# Peripheral.net
KiCad netlist of a schematic drawn in EAGLE
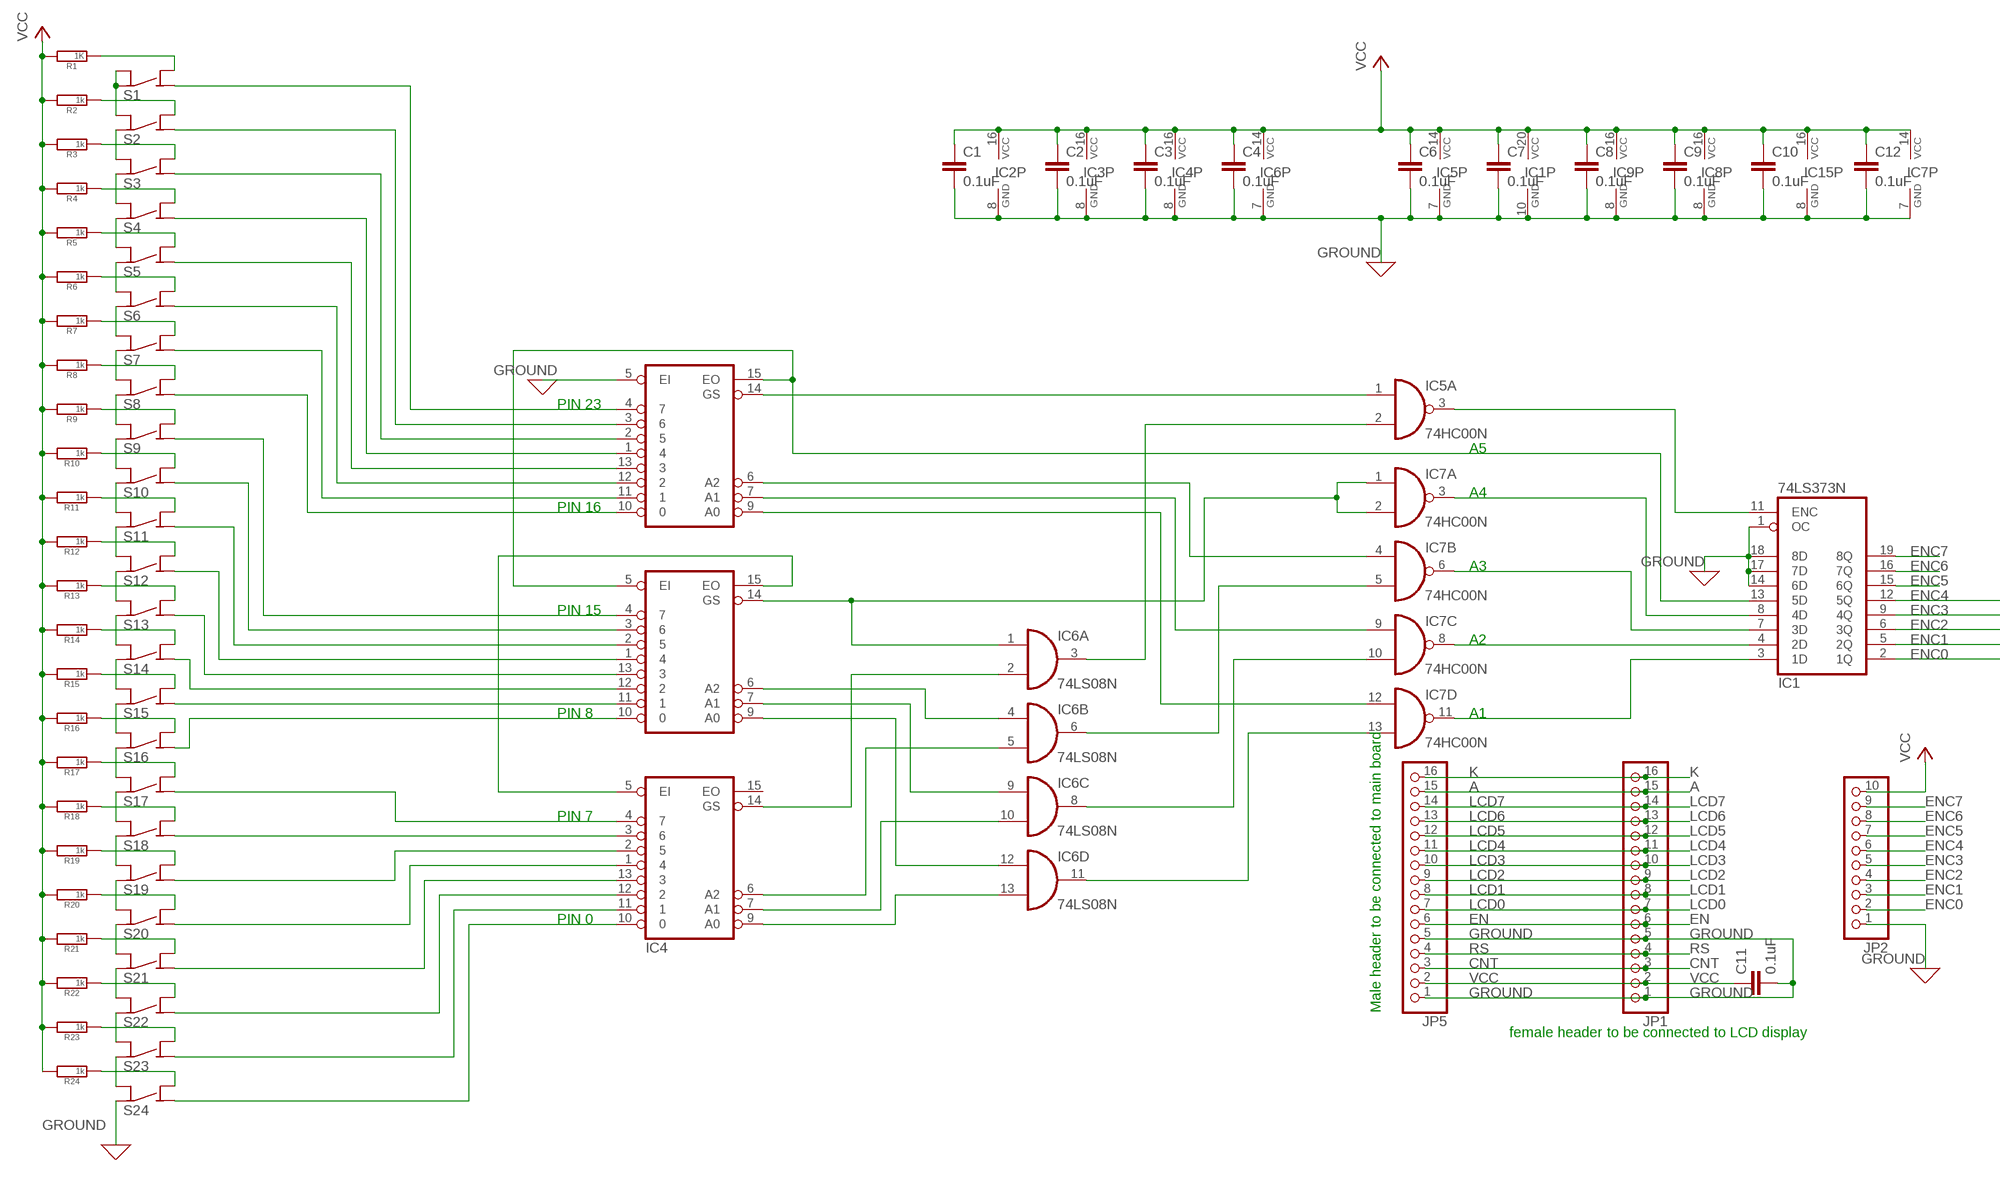
[diagram p0: schematic, sheet 1, part 1 of 2]
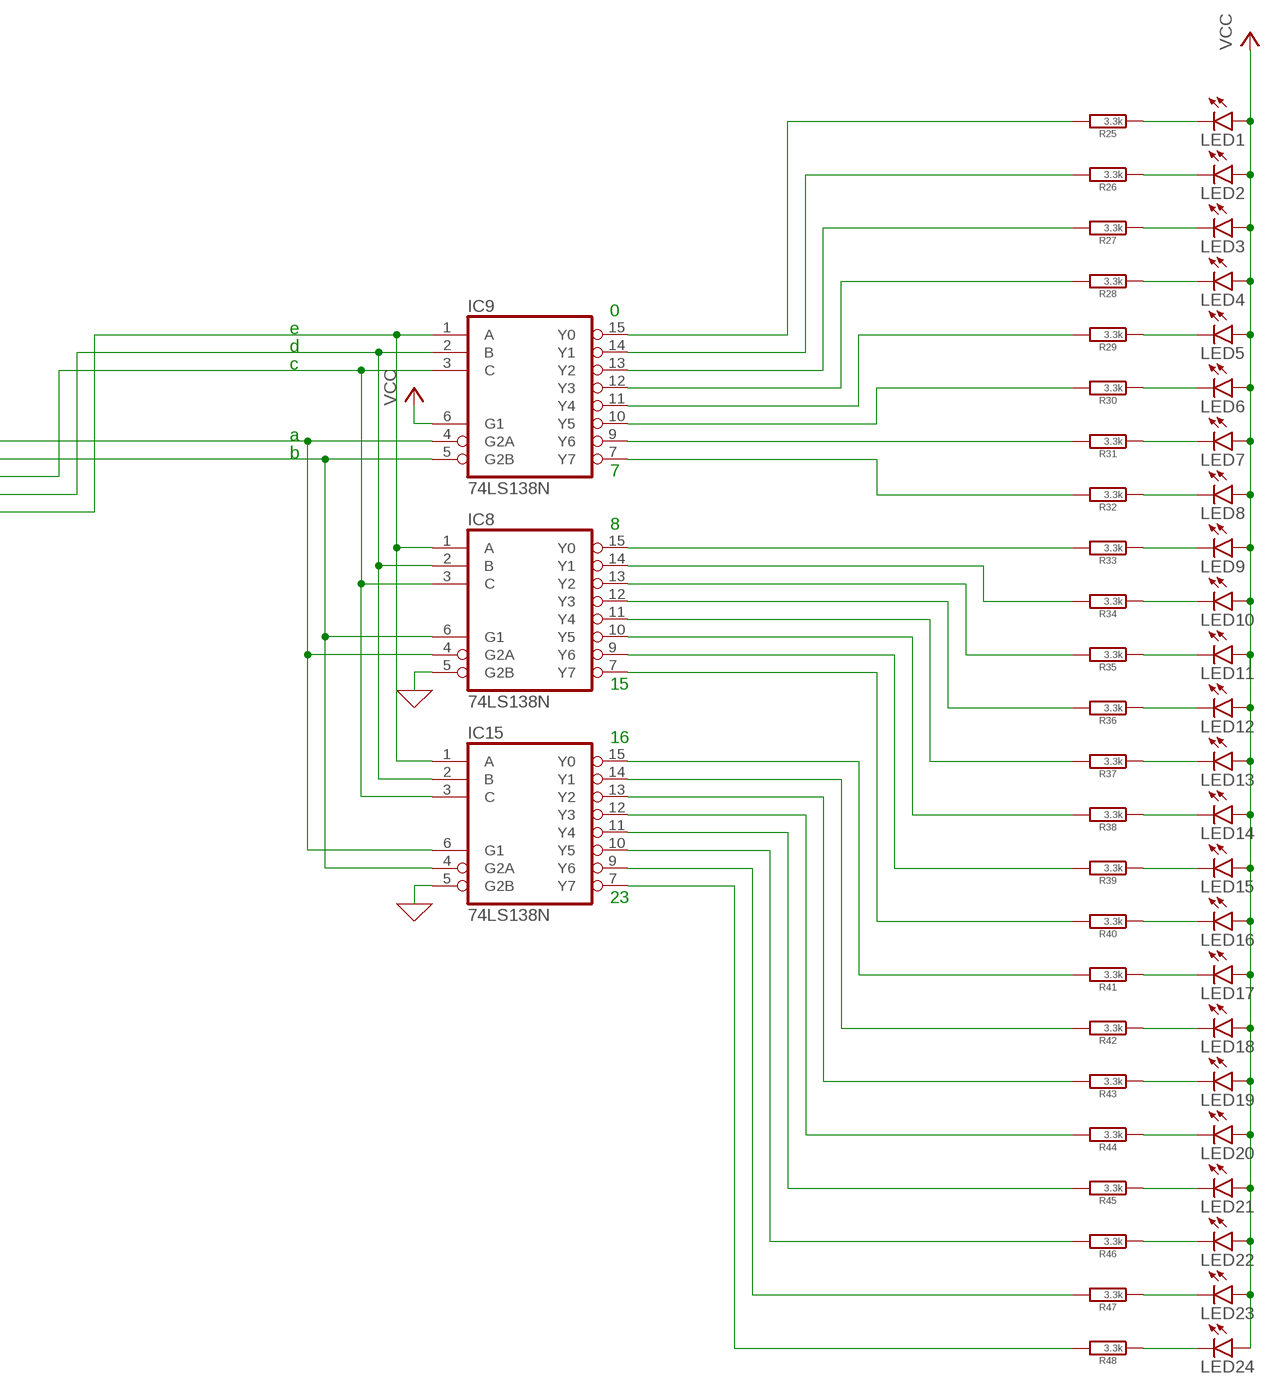
[diagram p1: schematic, sheet 1, part 2 of 2]

(export (version "E")
  (design (tool "Eeschema 10.0.6"))
  (components
    (comp (ref "C1")
      (value "0.1uF")
      (footprint "eagle-import:C2.5-2")
      (libsource (lib "eagle-import") (part "C2.5/2"))
    )
    (comp (ref "C2")
      (value "0.1uF")
      (footprint "eagle-import:C2.5-2")
      (libsource (lib "eagle-import") (part "C2.5/2"))
    )
    (comp (ref "C3")
      (value "0.1uF")
      (footprint "eagle-import:C2.5-2")
      (libsource (lib "eagle-import") (part "C2.5/2"))
    )
    (comp (ref "C4")
      (value "0.1uF")
      (footprint "eagle-import:C2.5-2")
      (libsource (lib "eagle-import") (part "C2.5/2"))
    )
    (comp (ref "C6")
      (value "0.1uF")
      (footprint "eagle-import:C2.5-2")
      (libsource (lib "eagle-import") (part "C2.5/2"))
    )
    (comp (ref "C7")
      (value "0.1uF")
      (footprint "eagle-import:C2.5-2")
      (libsource (lib "eagle-import") (part "C2.5/2"))
    )
    (comp (ref "C8")
      (value "0.1uF")
      (footprint "eagle-import:C2.5-2")
      (libsource (lib "eagle-import") (part "C2.5/2"))
    )
    (comp (ref "C9")
      (value "0.1uF")
      (footprint "eagle-import:C2.5-2")
      (libsource (lib "eagle-import") (part "C2.5/2"))
    )
    (comp (ref "C10")
      (value "0.1uF")
      (footprint "eagle-import:C2.5-2")
      (libsource (lib "eagle-import") (part "C2.5/2"))
    )
    (comp (ref "C11")
      (value "0.1uF")
      (footprint "eagle-import:C025-025X050")
      (libsource (lib "eagle-import") (part "C-EU025-025X050"))
    )
    (comp (ref "C12")
      (value "0.1uF")
      (footprint "eagle-import:C2.5-2")
      (libsource (lib "eagle-import") (part "C2.5/2"))
    )
    (comp (ref "IC1")
      (value "74LS373N")
      (footprint "eagle-import:DIL20")
      (libsource (lib "eagle-import") (part "74373NLS"))
    )
    (comp (ref "IC2")
      (value "74HC148N")
      (footprint "eagle-import:DIL16")
      (libsource (lib "eagle-import") (part "74148NHC"))
    )
    (comp (ref "IC3")
      (value "74HC148N")
      (footprint "eagle-import:DIL16")
      (libsource (lib "eagle-import") (part "74148NHC"))
    )
    (comp (ref "IC4")
      (value "74HC148N")
      (footprint "eagle-import:DIL16")
      (libsource (lib "eagle-import") (part "74148NHC"))
    )
    (comp (ref "IC5")
      (value "74HC00N")
      (footprint "eagle-import:DIL14")
      (libsource (lib "eagle-import") (part "7400NHC"))
    )
    (comp (ref "IC6")
      (value "74LS08N")
      (footprint "eagle-import:DIL14")
      (libsource (lib "eagle-import") (part "7408NLS"))
    )
    (comp (ref "IC7")
      (value "74HC00N")
      (footprint "eagle-import:DIL14")
      (libsource (lib "eagle-import") (part "7400NHC"))
    )
    (comp (ref "IC8")
      (value "74LS138N")
      (footprint "eagle-import:DIL16")
      (libsource (lib "eagle-import") (part "74138NLS"))
    )
    (comp (ref "IC9")
      (value "74LS138N")
      (footprint "eagle-import:DIL16")
      (libsource (lib "eagle-import") (part "74138NLS"))
    )
    (comp (ref "IC15")
      (value "74LS138N")
      (footprint "eagle-import:DIL16")
      (libsource (lib "eagle-import") (part "74138NLS"))
    )
    (comp (ref "JP1")
      (value "PINHD-1X16")
      (footprint "eagle-import:1X16")
      (libsource (lib "eagle-import") (part "PINHD-1X16"))
    )
    (comp (ref "JP2")
      (value "PINHD-1X10")
      (footprint "eagle-import:1X10")
      (libsource (lib "eagle-import") (part "PINHD-1X10"))
    )
    (comp (ref "JP5")
      (value "PINHD-1X16")
      (footprint "eagle-import:1X16")
      (libsource (lib "eagle-import") (part "PINHD-1X16"))
    )
    (comp (ref "LED1")
      (value "LED5MM")
      (footprint "eagle-import:LED5MM")
      (libsource (lib "eagle-import") (part "LED5MM"))
    )
    (comp (ref "LED2")
      (value "LED5MM")
      (footprint "eagle-import:LED5MM")
      (libsource (lib "eagle-import") (part "LED5MM"))
    )
    (comp (ref "LED3")
      (value "LED5MM")
      (footprint "eagle-import:LED5MM")
      (libsource (lib "eagle-import") (part "LED5MM"))
    )
    (comp (ref "LED4")
      (value "LED5MM")
      (footprint "eagle-import:LED5MM")
      (libsource (lib "eagle-import") (part "LED5MM"))
    )
    (comp (ref "LED5")
      (value "LED5MM")
      (footprint "eagle-import:LED5MM")
      (libsource (lib "eagle-import") (part "LED5MM"))
    )
    (comp (ref "LED6")
      (value "LED5MM")
      (footprint "eagle-import:LED5MM")
      (libsource (lib "eagle-import") (part "LED5MM"))
    )
    (comp (ref "LED7")
      (value "LED5MM")
      (footprint "eagle-import:LED5MM")
      (libsource (lib "eagle-import") (part "LED5MM"))
    )
    (comp (ref "LED8")
      (value "LED5MM")
      (footprint "eagle-import:LED5MM")
      (libsource (lib "eagle-import") (part "LED5MM"))
    )
    (comp (ref "LED9")
      (value "LED5MM")
      (footprint "eagle-import:LED5MM")
      (libsource (lib "eagle-import") (part "LED5MM"))
    )
    (comp (ref "LED10")
      (value "LED5MM")
      (footprint "eagle-import:LED5MM")
      (libsource (lib "eagle-import") (part "LED5MM"))
    )
    (comp (ref "LED11")
      (value "LED5MM")
      (footprint "eagle-import:LED5MM")
      (libsource (lib "eagle-import") (part "LED5MM"))
    )
    (comp (ref "LED12")
      (value "LED5MM")
      (footprint "eagle-import:LED5MM")
      (libsource (lib "eagle-import") (part "LED5MM"))
    )
    (comp (ref "LED13")
      (value "LED5MM")
      (footprint "eagle-import:LED5MM")
      (libsource (lib "eagle-import") (part "LED5MM"))
    )
    (comp (ref "LED14")
      (value "LED5MM")
      (footprint "eagle-import:LED5MM")
      (libsource (lib "eagle-import") (part "LED5MM"))
    )
    (comp (ref "LED15")
      (value "LED5MM")
      (footprint "eagle-import:LED5MM")
      (libsource (lib "eagle-import") (part "LED5MM"))
    )
    (comp (ref "LED16")
      (value "LED5MM")
      (footprint "eagle-import:LED5MM")
      (libsource (lib "eagle-import") (part "LED5MM"))
    )
    (comp (ref "LED17")
      (value "LED5MM")
      (footprint "eagle-import:LED5MM")
      (libsource (lib "eagle-import") (part "LED5MM"))
    )
    (comp (ref "LED18")
      (value "LED5MM")
      (footprint "eagle-import:LED5MM")
      (libsource (lib "eagle-import") (part "LED5MM"))
    )
    (comp (ref "LED19")
      (value "LED5MM")
      (footprint "eagle-import:LED5MM")
      (libsource (lib "eagle-import") (part "LED5MM"))
    )
    (comp (ref "LED20")
      (value "LED5MM")
      (footprint "eagle-import:LED5MM")
      (libsource (lib "eagle-import") (part "LED5MM"))
    )
    (comp (ref "LED21")
      (value "LED5MM")
      (footprint "eagle-import:LED5MM")
      (libsource (lib "eagle-import") (part "LED5MM"))
    )
    (comp (ref "LED22")
      (value "LED5MM")
      (footprint "eagle-import:LED5MM")
      (libsource (lib "eagle-import") (part "LED5MM"))
    )
    (comp (ref "LED23")
      (value "LED5MM")
      (footprint "eagle-import:LED5MM")
      (libsource (lib "eagle-import") (part "LED5MM"))
    )
    (comp (ref "LED24")
      (value "LED5MM")
      (footprint "eagle-import:LED5MM")
      (libsource (lib "eagle-import") (part "LED5MM"))
    )
    (comp (ref "R1")
      (value "1K")
      (footprint "eagle-import:1_6W(5MM)")
      (libsource (lib "eagle-import") (part "R{gt}{gt}1/6W(5MM)"))
    )
    (comp (ref "R2")
      (value "1k")
      (footprint "eagle-import:1_6W(5MM)")
      (libsource (lib "eagle-import") (part "R{gt}{gt}1/6W(5MM)"))
    )
    (comp (ref "R3")
      (value "1k")
      (footprint "eagle-import:1_6W(5MM)")
      (libsource (lib "eagle-import") (part "R{gt}{gt}1/6W(5MM)"))
    )
    (comp (ref "R4")
      (value "1k")
      (footprint "eagle-import:1_6W(5MM)")
      (libsource (lib "eagle-import") (part "R{gt}{gt}1/6W(5MM)"))
    )
    (comp (ref "R5")
      (value "1k")
      (footprint "eagle-import:1_6W(5MM)")
      (libsource (lib "eagle-import") (part "R{gt}{gt}1/6W(5MM)"))
    )
    (comp (ref "R6")
      (value "1k")
      (footprint "eagle-import:1_6W(5MM)")
      (libsource (lib "eagle-import") (part "R{gt}{gt}1/6W(5MM)"))
    )
    (comp (ref "R7")
      (value "1k")
      (footprint "eagle-import:1_6W(5MM)")
      (libsource (lib "eagle-import") (part "R{gt}{gt}1/6W(5MM)"))
    )
    (comp (ref "R8")
      (value "1k")
      (footprint "eagle-import:1_6W(5MM)")
      (libsource (lib "eagle-import") (part "R{gt}{gt}1/6W(5MM)"))
    )
    (comp (ref "R9")
      (value "1k")
      (footprint "eagle-import:1_6W(5MM)")
      (libsource (lib "eagle-import") (part "R{gt}{gt}1/6W(5MM)"))
    )
    (comp (ref "R10")
      (value "1k")
      (footprint "eagle-import:1_6W(5MM)")
      (libsource (lib "eagle-import") (part "R{gt}{gt}1/6W(5MM)"))
    )
    (comp (ref "R11")
      (value "1k")
      (footprint "eagle-import:1_6W(5MM)")
      (libsource (lib "eagle-import") (part "R{gt}{gt}1/6W(5MM)"))
    )
    (comp (ref "R12")
      (value "1k")
      (footprint "eagle-import:1_6W(5MM)")
      (libsource (lib "eagle-import") (part "R{gt}{gt}1/6W(5MM)"))
    )
    (comp (ref "R13")
      (value "1k")
      (footprint "eagle-import:1_6W(5MM)")
      (libsource (lib "eagle-import") (part "R{gt}{gt}1/6W(5MM)"))
    )
    (comp (ref "R14")
      (value "1k")
      (footprint "eagle-import:1_6W(5MM)")
      (libsource (lib "eagle-import") (part "R{gt}{gt}1/6W(5MM)"))
    )
    (comp (ref "R15")
      (value "1k")
      (footprint "eagle-import:1_6W(5MM)")
      (libsource (lib "eagle-import") (part "R{gt}{gt}1/6W(5MM)"))
    )
    (comp (ref "R16")
      (value "1k")
      (footprint "eagle-import:1_6W(5MM)")
      (libsource (lib "eagle-import") (part "R{gt}{gt}1/6W(5MM)"))
    )
    (comp (ref "R17")
      (value "1k")
      (footprint "eagle-import:1_6W(5MM)")
      (libsource (lib "eagle-import") (part "R{gt}{gt}1/6W(5MM)"))
    )
    (comp (ref "R18")
      (value "1k")
      (footprint "eagle-import:1_6W(5MM)")
      (libsource (lib "eagle-import") (part "R{gt}{gt}1/6W(5MM)"))
    )
    (comp (ref "R19")
      (value "1k")
      (footprint "eagle-import:1_6W(5MM)")
      (libsource (lib "eagle-import") (part "R{gt}{gt}1/6W(5MM)"))
    )
    (comp (ref "R20")
      (value "1k")
      (footprint "eagle-import:1_6W(5MM)")
      (libsource (lib "eagle-import") (part "R{gt}{gt}1/6W(5MM)"))
    )
    (comp (ref "R21")
      (value "1k")
      (footprint "eagle-import:1_6W(5MM)")
      (libsource (lib "eagle-import") (part "R{gt}{gt}1/6W(5MM)"))
    )
    (comp (ref "R22")
      (value "1k")
      (footprint "eagle-import:1_6W(5MM)")
      (libsource (lib "eagle-import") (part "R{gt}{gt}1/6W(5MM)"))
    )
    (comp (ref "R23")
      (value "1k")
      (footprint "eagle-import:1_6W(5MM)")
      (libsource (lib "eagle-import") (part "R{gt}{gt}1/6W(5MM)"))
    )
    (comp (ref "R24")
      (value "1k")
      (footprint "eagle-import:1_6W(5MM)")
      (libsource (lib "eagle-import") (part "R{gt}{gt}1/6W(5MM)"))
    )
    (comp (ref "R25")
      (value "3.3k")
      (footprint "eagle-import:1_6W(5MM)")
      (libsource (lib "eagle-import") (part "R{gt}{gt}1/6W(5MM)"))
    )
    (comp (ref "R26")
      (value "3.3k")
      (footprint "eagle-import:1_6W(5MM)")
      (libsource (lib "eagle-import") (part "R{gt}{gt}1/6W(5MM)"))
    )
    (comp (ref "R27")
      (value "3.3k")
      (footprint "eagle-import:1_6W(5MM)")
      (libsource (lib "eagle-import") (part "R{gt}{gt}1/6W(5MM)"))
    )
    (comp (ref "R28")
      (value "3.3k")
      (footprint "eagle-import:1_6W(5MM)")
      (libsource (lib "eagle-import") (part "R{gt}{gt}1/6W(5MM)"))
    )
    (comp (ref "R29")
      (value "3.3k")
      (footprint "eagle-import:1_6W(5MM)")
      (libsource (lib "eagle-import") (part "R{gt}{gt}1/6W(5MM)"))
    )
    (comp (ref "R30")
      (value "3.3k")
      (footprint "eagle-import:1_6W(5MM)")
      (libsource (lib "eagle-import") (part "R{gt}{gt}1/6W(5MM)"))
    )
    (comp (ref "R31")
      (value "3.3k")
      (footprint "eagle-import:1_6W(5MM)")
      (libsource (lib "eagle-import") (part "R{gt}{gt}1/6W(5MM)"))
    )
    (comp (ref "R32")
      (value "3.3k")
      (footprint "eagle-import:1_6W(5MM)")
      (libsource (lib "eagle-import") (part "R{gt}{gt}1/6W(5MM)"))
    )
    (comp (ref "R33")
      (value "3.3k")
      (footprint "eagle-import:1_6W(5MM)")
      (libsource (lib "eagle-import") (part "R{gt}{gt}1/6W(5MM)"))
    )
    (comp (ref "R34")
      (value "3.3k")
      (footprint "eagle-import:1_6W(5MM)")
      (libsource (lib "eagle-import") (part "R{gt}{gt}1/6W(5MM)"))
    )
    (comp (ref "R35")
      (value "3.3k")
      (footprint "eagle-import:1_6W(5MM)")
      (libsource (lib "eagle-import") (part "R{gt}{gt}1/6W(5MM)"))
    )
    (comp (ref "R36")
      (value "3.3k")
      (footprint "eagle-import:1_6W(5MM)")
      (libsource (lib "eagle-import") (part "R{gt}{gt}1/6W(5MM)"))
    )
    (comp (ref "R37")
      (value "3.3k")
      (footprint "eagle-import:1_6W(5MM)")
      (libsource (lib "eagle-import") (part "R{gt}{gt}1/6W(5MM)"))
    )
    (comp (ref "R38")
      (value "3.3k")
      (footprint "eagle-import:1_6W(5MM)")
      (libsource (lib "eagle-import") (part "R{gt}{gt}1/6W(5MM)"))
    )
    (comp (ref "R39")
      (value "3.3k")
      (footprint "eagle-import:1_6W(5MM)")
      (libsource (lib "eagle-import") (part "R{gt}{gt}1/6W(5MM)"))
    )
    (comp (ref "R40")
      (value "3.3k")
      (footprint "eagle-import:1_6W(5MM)")
      (libsource (lib "eagle-import") (part "R{gt}{gt}1/6W(5MM)"))
    )
    (comp (ref "R41")
      (value "3.3k")
      (footprint "eagle-import:1_6W(5MM)")
      (libsource (lib "eagle-import") (part "R{gt}{gt}1/6W(5MM)"))
    )
    (comp (ref "R42")
      (value "3.3k")
      (footprint "eagle-import:1_6W(5MM)")
      (libsource (lib "eagle-import") (part "R{gt}{gt}1/6W(5MM)"))
    )
    (comp (ref "R43")
      (value "3.3k")
      (footprint "eagle-import:1_6W(5MM)")
      (libsource (lib "eagle-import") (part "R{gt}{gt}1/6W(5MM)"))
    )
    (comp (ref "R44")
      (value "3.3k")
      (footprint "eagle-import:1_6W(5MM)")
      (libsource (lib "eagle-import") (part "R{gt}{gt}1/6W(5MM)"))
    )
    (comp (ref "R45")
      (value "3.3k")
      (footprint "eagle-import:1_6W(5MM)")
      (libsource (lib "eagle-import") (part "R{gt}{gt}1/6W(5MM)"))
    )
    (comp (ref "R46")
      (value "3.3k")
      (footprint "eagle-import:1_6W(5MM)")
      (libsource (lib "eagle-import") (part "R{gt}{gt}1/6W(5MM)"))
    )
    (comp (ref "R47")
      (value "3.3k")
      (footprint "eagle-import:1_6W(5MM)")
      (libsource (lib "eagle-import") (part "R{gt}{gt}1/6W(5MM)"))
    )
    (comp (ref "R48")
      (value "3.3k")
      (footprint "eagle-import:1_6W(5MM)")
      (libsource (lib "eagle-import") (part "R{gt}{gt}1/6W(5MM)"))
    )
    (comp (ref "S1")
      (value "SPST4B3F-10XX")
      (footprint "eagle-import:B3F-10XX")
      (libsource (lib "eagle-import") (part "SPST4B3F-10XX"))
    )
    (comp (ref "S2")
      (value "SPST4B3F-10XX")
      (footprint "eagle-import:B3F-10XX")
      (libsource (lib "eagle-import") (part "SPST4B3F-10XX"))
    )
    (comp (ref "S3")
      (value "SPST4B3F-10XX")
      (footprint "eagle-import:B3F-10XX")
      (libsource (lib "eagle-import") (part "SPST4B3F-10XX"))
    )
    (comp (ref "S4")
      (value "SPST4B3F-10XX")
      (footprint "eagle-import:B3F-10XX")
      (libsource (lib "eagle-import") (part "SPST4B3F-10XX"))
    )
    (comp (ref "S5")
      (value "SPST4B3F-10XX")
      (footprint "eagle-import:B3F-10XX")
      (libsource (lib "eagle-import") (part "SPST4B3F-10XX"))
    )
    (comp (ref "S6")
      (value "SPST4B3F-10XX")
      (footprint "eagle-import:B3F-10XX")
      (libsource (lib "eagle-import") (part "SPST4B3F-10XX"))
    )
    (comp (ref "S7")
      (value "SPST4B3F-10XX")
      (footprint "eagle-import:B3F-10XX")
      (libsource (lib "eagle-import") (part "SPST4B3F-10XX"))
    )
    (comp (ref "S8")
      (value "SPST4B3F-10XX")
      (footprint "eagle-import:B3F-10XX")
      (libsource (lib "eagle-import") (part "SPST4B3F-10XX"))
    )
    (comp (ref "S9")
      (value "SPST4B3F-10XX")
      (footprint "eagle-import:B3F-10XX")
      (libsource (lib "eagle-import") (part "SPST4B3F-10XX"))
    )
    (comp (ref "S10")
      (value "SPST4B3F-10XX")
      (footprint "eagle-import:B3F-10XX")
      (libsource (lib "eagle-import") (part "SPST4B3F-10XX"))
    )
    (comp (ref "S11")
      (value "SPST4B3F-10XX")
      (footprint "eagle-import:B3F-10XX")
      (libsource (lib "eagle-import") (part "SPST4B3F-10XX"))
    )
    (comp (ref "S12")
      (value "SPST4B3F-10XX")
      (footprint "eagle-import:B3F-10XX")
      (libsource (lib "eagle-import") (part "SPST4B3F-10XX"))
    )
    (comp (ref "S13")
      (value "SPST4B3F-10XX")
      (footprint "eagle-import:B3F-10XX")
      (libsource (lib "eagle-import") (part "SPST4B3F-10XX"))
    )
    (comp (ref "S14")
      (value "SPST4B3F-10XX")
      (footprint "eagle-import:B3F-10XX")
      (libsource (lib "eagle-import") (part "SPST4B3F-10XX"))
    )
    (comp (ref "S15")
      (value "SPST4B3F-10XX")
      (footprint "eagle-import:B3F-10XX")
      (libsource (lib "eagle-import") (part "SPST4B3F-10XX"))
    )
    (comp (ref "S16")
      (value "SPST4B3F-10XX")
      (footprint "eagle-import:B3F-10XX")
      (libsource (lib "eagle-import") (part "SPST4B3F-10XX"))
    )
    (comp (ref "S17")
      (value "SPST4B3F-10XX")
      (footprint "eagle-import:B3F-10XX")
      (libsource (lib "eagle-import") (part "SPST4B3F-10XX"))
    )
    (comp (ref "S18")
      (value "SPST4B3F-10XX")
      (footprint "eagle-import:B3F-10XX")
      (libsource (lib "eagle-import") (part "SPST4B3F-10XX"))
    )
    (comp (ref "S19")
      (value "SPST4B3F-10XX")
      (footprint "eagle-import:B3F-10XX")
      (libsource (lib "eagle-import") (part "SPST4B3F-10XX"))
    )
    (comp (ref "S20")
      (value "SPST4B3F-10XX")
      (footprint "eagle-import:B3F-10XX")
      (libsource (lib "eagle-import") (part "SPST4B3F-10XX"))
    )
    (comp (ref "S21")
      (value "SPST4B3F-10XX")
      (footprint "eagle-import:B3F-10XX")
      (libsource (lib "eagle-import") (part "SPST4B3F-10XX"))
    )
    (comp (ref "S22")
      (value "SPST4B3F-10XX")
      (footprint "eagle-import:B3F-10XX")
      (libsource (lib "eagle-import") (part "SPST4B3F-10XX"))
    )
    (comp (ref "S23")
      (value "SPST4B3F-10XX")
      (footprint "eagle-import:B3F-10XX")
      (libsource (lib "eagle-import") (part "SPST4B3F-10XX"))
    )
    (comp (ref "S24")
      (value "SPST4B3F-10XX")
      (footprint "eagle-import:B3F-10XX")
      (libsource (lib "eagle-import") (part "SPST4B3F-10XX"))
    )
  )
  (nets
    (net (code "1") (name "/A") (class "Default")
      (node (ref "JP1") (pin "15") (pinfunction "15_15") (pintype "passive"))
      (node (ref "JP5") (pin "15") (pinfunction "15_15") (pintype "passive"))
    )
    (net (code "2") (name "/CNT") (class "Default")
      (node (ref "JP1") (pin "3") (pinfunction "3_3") (pintype "passive"))
      (node (ref "JP5") (pin "3") (pinfunction "3_3") (pintype "passive"))
    )
    (net (code "3") (name "/EN") (class "Default")
      (node (ref "JP1") (pin "6") (pinfunction "6_6") (pintype "passive"))
      (node (ref "JP5") (pin "6") (pinfunction "6_6") (pintype "passive"))
    )
    (net (code "4") (name "/ENC0") (class "Default")
      (node (ref "IC1") (pin "2") (pinfunction "1Q_2") (pintype "tri_state"))
      (node (ref "IC15") (pin "1") (pinfunction "A_1") (pintype "input"))
      (node (ref "IC8") (pin "1") (pinfunction "A_1") (pintype "input"))
      (node (ref "IC9") (pin "1") (pinfunction "A_1") (pintype "input"))
      (node (ref "JP2") (pin "2") (pinfunction "2_2") (pintype "passive"))
    )
    (net (code "5") (name "/ENC1") (class "Default")
      (node (ref "IC1") (pin "5") (pinfunction "2Q_5") (pintype "tri_state"))
      (node (ref "IC15") (pin "2") (pinfunction "B_2") (pintype "input"))
      (node (ref "IC8") (pin "2") (pinfunction "B_2") (pintype "input"))
      (node (ref "IC9") (pin "2") (pinfunction "B_2") (pintype "input"))
      (node (ref "JP2") (pin "3") (pinfunction "3_3") (pintype "passive"))
    )
    (net (code "6") (name "/ENC2") (class "Default")
      (node (ref "IC1") (pin "6") (pinfunction "3Q_6") (pintype "tri_state"))
      (node (ref "IC15") (pin "3") (pinfunction "C_3") (pintype "input"))
      (node (ref "IC8") (pin "3") (pinfunction "C_3") (pintype "input"))
      (node (ref "IC9") (pin "3") (pinfunction "C_3") (pintype "input"))
      (node (ref "JP2") (pin "4") (pinfunction "4_4") (pintype "passive"))
    )
    (net (code "7") (name "/ENC3") (class "Default")
      (node (ref "IC1") (pin "9") (pinfunction "4Q_9") (pintype "tri_state"))
      (node (ref "IC15") (pin "4") (pinfunction "G2A_4") (pintype "input"))
      (node (ref "IC8") (pin "6") (pinfunction "G1_6") (pintype "input"))
      (node (ref "IC9") (pin "5") (pinfunction "G2B_5") (pintype "input"))
      (node (ref "JP2") (pin "5") (pinfunction "5_5") (pintype "passive"))
    )
    (net (code "8") (name "/ENC4") (class "Default")
      (node (ref "IC1") (pin "12") (pinfunction "5Q_12") (pintype "tri_state"))
      (node (ref "IC15") (pin "6") (pinfunction "G1_6") (pintype "input"))
      (node (ref "IC8") (pin "4") (pinfunction "G2A_4") (pintype "input"))
      (node (ref "IC9") (pin "4") (pinfunction "G2A_4") (pintype "input"))
      (node (ref "JP2") (pin "6") (pinfunction "6_6") (pintype "passive"))
    )
    (net (code "9") (name "/ENC5") (class "Default")
      (node (ref "IC1") (pin "15") (pinfunction "6Q_15") (pintype "tri_state"))
      (node (ref "JP2") (pin "7") (pinfunction "7_7") (pintype "passive"))
    )
    (net (code "10") (name "/ENC6") (class "Default")
      (node (ref "IC1") (pin "16") (pinfunction "7Q_16") (pintype "tri_state"))
      (node (ref "JP2") (pin "8") (pinfunction "8_8") (pintype "passive"))
    )
    (net (code "11") (name "/ENC7") (class "Default")
      (node (ref "IC1") (pin "19") (pinfunction "8Q_19") (pintype "tri_state"))
      (node (ref "JP2") (pin "9") (pinfunction "9_9") (pintype "passive"))
    )
    (net (code "12") (name "/K") (class "Default")
      (node (ref "JP1") (pin "16") (pinfunction "16_16") (pintype "passive"))
      (node (ref "JP5") (pin "16") (pinfunction "16_16") (pintype "passive"))
    )
    (net (code "13") (name "/LCD0") (class "Default")
      (node (ref "JP1") (pin "7") (pinfunction "7_7") (pintype "passive"))
      (node (ref "JP5") (pin "7") (pinfunction "7_7") (pintype "passive"))
    )
    (net (code "14") (name "/LCD1") (class "Default")
      (node (ref "JP1") (pin "8") (pinfunction "8_8") (pintype "passive"))
      (node (ref "JP5") (pin "8") (pinfunction "8_8") (pintype "passive"))
    )
    (net (code "15") (name "/LCD2") (class "Default")
      (node (ref "JP1") (pin "9") (pinfunction "9_9") (pintype "passive"))
      (node (ref "JP5") (pin "9") (pinfunction "9_9") (pintype "passive"))
    )
    (net (code "16") (name "/LCD3") (class "Default")
      (node (ref "JP1") (pin "10") (pinfunction "10_10") (pintype "passive"))
      (node (ref "JP5") (pin "10") (pinfunction "10_10") (pintype "passive"))
    )
    (net (code "17") (name "/LCD4") (class "Default")
      (node (ref "JP1") (pin "11") (pinfunction "11_11") (pintype "passive"))
      (node (ref "JP5") (pin "11") (pinfunction "11_11") (pintype "passive"))
    )
    (net (code "18") (name "/LCD5") (class "Default")
      (node (ref "JP1") (pin "12") (pinfunction "12_12") (pintype "passive"))
      (node (ref "JP5") (pin "12") (pinfunction "12_12") (pintype "passive"))
    )
    (net (code "19") (name "/LCD6") (class "Default")
      (node (ref "JP1") (pin "13") (pinfunction "13_13") (pintype "passive"))
      (node (ref "JP5") (pin "13") (pinfunction "13_13") (pintype "passive"))
    )
    (net (code "20") (name "/LCD7") (class "Default")
      (node (ref "JP1") (pin "14") (pinfunction "14_14") (pintype "passive"))
      (node (ref "JP5") (pin "14") (pinfunction "14_14") (pintype "passive"))
    )
    (net (code "21") (name "/RS") (class "Default")
      (node (ref "JP1") (pin "4") (pinfunction "4_4") (pintype "passive"))
      (node (ref "JP5") (pin "4") (pinfunction "4_4") (pintype "passive"))
    )
    (net (code "22") (name "GND") (class "Default")
      (node (ref "C1") (pin "2") (pinfunction "2_2") (pintype "passive"))
      (node (ref "C10") (pin "2") (pinfunction "2_2") (pintype "passive"))
      (node (ref "C11") (pin "2") (pinfunction "2_2") (pintype "passive"))
      (node (ref "C12") (pin "2") (pinfunction "2_2") (pintype "passive"))
      (node (ref "C2") (pin "2") (pinfunction "2_2") (pintype "passive"))
      (node (ref "C3") (pin "2") (pinfunction "2_2") (pintype "passive"))
      (node (ref "C4") (pin "2") (pinfunction "2_2") (pintype "passive"))
      (node (ref "C6") (pin "2") (pinfunction "2_2") (pintype "passive"))
      (node (ref "C7") (pin "2") (pinfunction "2_2") (pintype "passive"))
      (node (ref "C8") (pin "2") (pinfunction "2_2") (pintype "passive"))
      (node (ref "C9") (pin "2") (pinfunction "2_2") (pintype "passive"))
      (node (ref "IC1") (pin "1") (pinfunction "OC_1") (pintype "input"))
      (node (ref "IC1") (pin "10") (pinfunction "GND_10") (pintype "power_in"))
      (node (ref "IC1") (pin "14") (pinfunction "6D_14") (pintype "input"))
      (node (ref "IC1") (pin "17") (pinfunction "7D_17") (pintype "input"))
      (node (ref "IC1") (pin "18") (pinfunction "8D_18") (pintype "input"))
      (node (ref "IC15") (pin "5") (pinfunction "G2B_5") (pintype "input"))
      (node (ref "IC15") (pin "8") (pinfunction "GND_8") (pintype "power_in"))
      (node (ref "IC2") (pin "5") (pinfunction "EI_5") (pintype "input"))
      (node (ref "IC2") (pin "8") (pinfunction "GND_8") (pintype "power_in"))
      (node (ref "IC3") (pin "8") (pinfunction "GND_8") (pintype "power_in"))
      (node (ref "IC4") (pin "8") (pinfunction "GND_8") (pintype "power_in"))
      (node (ref "IC5") (pin "7") (pinfunction "GND_7") (pintype "power_in"))
      (node (ref "IC6") (pin "7") (pinfunction "GND_7") (pintype "power_in"))
      (node (ref "IC7") (pin "7") (pinfunction "GND_7") (pintype "power_in"))
      (node (ref "IC8") (pin "5") (pinfunction "G2B_5") (pintype "input"))
      (node (ref "IC8") (pin "8") (pinfunction "GND_8") (pintype "power_in"))
      (node (ref "IC9") (pin "8") (pinfunction "GND_8") (pintype "power_in"))
      (node (ref "JP1") (pin "1") (pinfunction "1_1") (pintype "passive"))
      (node (ref "JP1") (pin "5") (pinfunction "5_5") (pintype "passive"))
      (node (ref "JP2") (pin "1") (pinfunction "1_1") (pintype "passive"))
      (node (ref "JP5") (pin "1") (pinfunction "1_1") (pintype "passive"))
      (node (ref "JP5") (pin "5") (pinfunction "5_5") (pintype "passive"))
      (node (ref "S1") (pin "COM@1") (pinfunction "COM_COM@1") (pintype "passive"))
      (node (ref "S1") (pin "COM@2") (pinfunction "COM_COM@2") (pintype "passive"))
      (node (ref "S10") (pin "COM@1") (pinfunction "COM_COM@1") (pintype "passive"))
      (node (ref "S10") (pin "COM@2") (pinfunction "COM_COM@2") (pintype "passive"))
      (node (ref "S11") (pin "COM@1") (pinfunction "COM_COM@1") (pintype "passive"))
      (node (ref "S11") (pin "COM@2") (pinfunction "COM_COM@2") (pintype "passive"))
      (node (ref "S12") (pin "COM@1") (pinfunction "COM_COM@1") (pintype "passive"))
      (node (ref "S12") (pin "COM@2") (pinfunction "COM_COM@2") (pintype "passive"))
      (node (ref "S13") (pin "COM@1") (pinfunction "COM_COM@1") (pintype "passive"))
      (node (ref "S13") (pin "COM@2") (pinfunction "COM_COM@2") (pintype "passive"))
      (node (ref "S14") (pin "COM@1") (pinfunction "COM_COM@1") (pintype "passive"))
      (node (ref "S14") (pin "COM@2") (pinfunction "COM_COM@2") (pintype "passive"))
      (node (ref "S15") (pin "COM@1") (pinfunction "COM_COM@1") (pintype "passive"))
      (node (ref "S15") (pin "COM@2") (pinfunction "COM_COM@2") (pintype "passive"))
      (node (ref "S16") (pin "COM@1") (pinfunction "COM_COM@1") (pintype "passive"))
      (node (ref "S16") (pin "COM@2") (pinfunction "COM_COM@2") (pintype "passive"))
      (node (ref "S17") (pin "COM@1") (pinfunction "COM_COM@1") (pintype "passive"))
      (node (ref "S17") (pin "COM@2") (pinfunction "COM_COM@2") (pintype "passive"))
      (node (ref "S18") (pin "COM@1") (pinfunction "COM_COM@1") (pintype "passive"))
      (node (ref "S18") (pin "COM@2") (pinfunction "COM_COM@2") (pintype "passive"))
      (node (ref "S19") (pin "COM@1") (pinfunction "COM_COM@1") (pintype "passive"))
      (node (ref "S19") (pin "COM@2") (pinfunction "COM_COM@2") (pintype "passive"))
      (node (ref "S2") (pin "COM@1") (pinfunction "COM_COM@1") (pintype "passive"))
      (node (ref "S2") (pin "COM@2") (pinfunction "COM_COM@2") (pintype "passive"))
      (node (ref "S20") (pin "COM@1") (pinfunction "COM_COM@1") (pintype "passive"))
      (node (ref "S20") (pin "COM@2") (pinfunction "COM_COM@2") (pintype "passive"))
      (node (ref "S21") (pin "COM@1") (pinfunction "COM_COM@1") (pintype "passive"))
      (node (ref "S21") (pin "COM@2") (pinfunction "COM_COM@2") (pintype "passive"))
      (node (ref "S22") (pin "COM@1") (pinfunction "COM_COM@1") (pintype "passive"))
      (node (ref "S22") (pin "COM@2") (pinfunction "COM_COM@2") (pintype "passive"))
      (node (ref "S23") (pin "COM@1") (pinfunction "COM_COM@1") (pintype "passive"))
      (node (ref "S23") (pin "COM@2") (pinfunction "COM_COM@2") (pintype "passive"))
      (node (ref "S24") (pin "COM@1") (pinfunction "COM_COM@1") (pintype "passive"))
      (node (ref "S24") (pin "COM@2") (pinfunction "COM_COM@2") (pintype "passive"))
      (node (ref "S3") (pin "COM@1") (pinfunction "COM_COM@1") (pintype "passive"))
      (node (ref "S3") (pin "COM@2") (pinfunction "COM_COM@2") (pintype "passive"))
      (node (ref "S4") (pin "COM@1") (pinfunction "COM_COM@1") (pintype "passive"))
      (node (ref "S4") (pin "COM@2") (pinfunction "COM_COM@2") (pintype "passive"))
      (node (ref "S5") (pin "COM@1") (pinfunction "COM_COM@1") (pintype "passive"))
      (node (ref "S5") (pin "COM@2") (pinfunction "COM_COM@2") (pintype "passive"))
      (node (ref "S6") (pin "COM@1") (pinfunction "COM_COM@1") (pintype "passive"))
      (node (ref "S6") (pin "COM@2") (pinfunction "COM_COM@2") (pintype "passive"))
      (node (ref "S7") (pin "COM@1") (pinfunction "COM_COM@1") (pintype "passive"))
      (node (ref "S7") (pin "COM@2") (pinfunction "COM_COM@2") (pintype "passive"))
      (node (ref "S8") (pin "COM@1") (pinfunction "COM_COM@1") (pintype "passive"))
      (node (ref "S8") (pin "COM@2") (pinfunction "COM_COM@2") (pintype "passive"))
      (node (ref "S9") (pin "COM@1") (pinfunction "COM_COM@1") (pintype "passive"))
      (node (ref "S9") (pin "COM@2") (pinfunction "COM_COM@2") (pintype "passive"))
    )
    (net (code "23") (name "Net-(IC1A-1D)") (class "Default")
      (node (ref "IC1") (pin "3") (pinfunction "1D_3") (pintype "input"))
      (node (ref "IC7") (pin "11") (pinfunction "O_11") (pintype "output"))
    )
    (net (code "24") (name "Net-(IC1A-2D)") (class "Default")
      (node (ref "IC1") (pin "4") (pinfunction "2D_4") (pintype "input"))
      (node (ref "IC7") (pin "8") (pinfunction "O_8") (pintype "output"))
    )
    (net (code "25") (name "Net-(IC1A-3D)") (class "Default")
      (node (ref "IC1") (pin "7") (pinfunction "3D_7") (pintype "input"))
      (node (ref "IC7") (pin "6") (pinfunction "O_6") (pintype "output"))
    )
    (net (code "26") (name "Net-(IC1A-4D)") (class "Default")
      (node (ref "IC1") (pin "8") (pinfunction "4D_8") (pintype "input"))
      (node (ref "IC7") (pin "3") (pinfunction "O_3") (pintype "output"))
    )
    (net (code "27") (name "Net-(IC1A-5D)") (class "Default")
      (node (ref "IC1") (pin "13") (pinfunction "5D_13") (pintype "input"))
      (node (ref "IC2") (pin "15") (pinfunction "EO_15") (pintype "output"))
      (node (ref "IC3") (pin "5") (pinfunction "EI_5") (pintype "input"))
    )
    (net (code "28") (name "Net-(IC1A-ENC)") (class "Default")
      (node (ref "IC1") (pin "11") (pinfunction "ENC_11") (pintype "input"))
      (node (ref "IC5") (pin "3") (pinfunction "O_3") (pintype "output"))
    )
    (net (code "29") (name "Net-(IC2A-0)") (class "Default")
      (node (ref "IC2") (pin "10") (pinfunction "0_10") (pintype "input"))
      (node (ref "S8") (pin "NO@1") (pinfunction "NO_NO@1") (pintype "passive"))
    )
    (net (code "30") (name "Net-(IC2A-1)") (class "Default")
      (node (ref "IC2") (pin "11") (pinfunction "1_11") (pintype "input"))
      (node (ref "S7") (pin "NO@1") (pinfunction "NO_NO@1") (pintype "passive"))
    )
    (net (code "31") (name "Net-(IC2A-2)") (class "Default")
      (node (ref "IC2") (pin "12") (pinfunction "2_12") (pintype "input"))
      (node (ref "S6") (pin "NO@1") (pinfunction "NO_NO@1") (pintype "passive"))
    )
    (net (code "32") (name "Net-(IC2A-3)") (class "Default")
      (node (ref "IC2") (pin "13") (pinfunction "3_13") (pintype "input"))
      (node (ref "S5") (pin "NO@1") (pinfunction "NO_NO@1") (pintype "passive"))
    )
    (net (code "33") (name "Net-(IC2A-4)") (class "Default")
      (node (ref "IC2") (pin "1") (pinfunction "4_1") (pintype "input"))
      (node (ref "S4") (pin "NO@1") (pinfunction "NO_NO@1") (pintype "passive"))
    )
    (net (code "34") (name "Net-(IC2A-5)") (class "Default")
      (node (ref "IC2") (pin "2") (pinfunction "5_2") (pintype "input"))
      (node (ref "S3") (pin "NO@1") (pinfunction "NO_NO@1") (pintype "passive"))
    )
    (net (code "35") (name "Net-(IC2A-6)") (class "Default")
      (node (ref "IC2") (pin "3") (pinfunction "6_3") (pintype "input"))
      (node (ref "S2") (pin "NO@1") (pinfunction "NO_NO@1") (pintype "passive"))
    )
    (net (code "36") (name "Net-(IC2A-7)") (class "Default")
      (node (ref "IC2") (pin "4") (pinfunction "7_4") (pintype "input"))
      (node (ref "S1") (pin "NO@1") (pinfunction "NO_NO@1") (pintype "passive"))
    )
    (net (code "37") (name "Net-(IC2A-A0)") (class "Default")
      (node (ref "IC2") (pin "9") (pinfunction "A0_9") (pintype "output"))
      (node (ref "IC7") (pin "12") (pinfunction "I0_12") (pintype "input"))
    )
    (net (code "38") (name "Net-(IC2A-A1)") (class "Default")
      (node (ref "IC2") (pin "7") (pinfunction "A1_7") (pintype "output"))
      (node (ref "IC7") (pin "9") (pinfunction "I0_9") (pintype "input"))
    )
    (net (code "39") (name "Net-(IC2A-A2)") (class "Default")
      (node (ref "IC2") (pin "6") (pinfunction "A2_6") (pintype "output"))
      (node (ref "IC7") (pin "4") (pinfunction "I0_4") (pintype "input"))
    )
    (net (code "40") (name "Net-(IC2A-GS)") (class "Default")
      (node (ref "IC2") (pin "14") (pinfunction "GS_14") (pintype "output"))
      (node (ref "IC5") (pin "1") (pinfunction "I0_1") (pintype "input"))
    )
    (net (code "41") (name "Net-(IC3A-0)") (class "Default")
      (node (ref "IC3") (pin "10") (pinfunction "0_10") (pintype "input"))
      (node (ref "S16") (pin "NO@1") (pinfunction "NO_NO@1") (pintype "passive"))
    )
    (net (code "42") (name "Net-(IC3A-1)") (class "Default")
      (node (ref "IC3") (pin "11") (pinfunction "1_11") (pintype "input"))
      (node (ref "S15") (pin "NO@1") (pinfunction "NO_NO@1") (pintype "passive"))
    )
    (net (code "43") (name "Net-(IC3A-2)") (class "Default")
      (node (ref "IC3") (pin "12") (pinfunction "2_12") (pintype "input"))
      (node (ref "S14") (pin "NO@1") (pinfunction "NO_NO@1") (pintype "passive"))
    )
    (net (code "44") (name "Net-(IC3A-3)") (class "Default")
      (node (ref "IC3") (pin "13") (pinfunction "3_13") (pintype "input"))
      (node (ref "S13") (pin "NO@1") (pinfunction "NO_NO@1") (pintype "passive"))
    )
    (net (code "45") (name "Net-(IC3A-4)") (class "Default")
      (node (ref "IC3") (pin "1") (pinfunction "4_1") (pintype "input"))
      (node (ref "S12") (pin "NO@1") (pinfunction "NO_NO@1") (pintype "passive"))
    )
    (net (code "46") (name "Net-(IC3A-5)") (class "Default")
      (node (ref "IC3") (pin "2") (pinfunction "5_2") (pintype "input"))
      (node (ref "S11") (pin "NO@1") (pinfunction "NO_NO@1") (pintype "passive"))
    )
    (net (code "47") (name "Net-(IC3A-6)") (class "Default")
      (node (ref "IC3") (pin "3") (pinfunction "6_3") (pintype "input"))
      (node (ref "S10") (pin "NO@1") (pinfunction "NO_NO@1") (pintype "passive"))
    )
    (net (code "48") (name "Net-(IC3A-7)") (class "Default")
      (node (ref "IC3") (pin "4") (pinfunction "7_4") (pintype "input"))
      (node (ref "S9") (pin "NO@1") (pinfunction "NO_NO@1") (pintype "passive"))
    )
    (net (code "49") (name "Net-(IC3A-A0)") (class "Default")
      (node (ref "IC3") (pin "9") (pinfunction "A0_9") (pintype "output"))
      (node (ref "IC6") (pin "12") (pinfunction "I0_12") (pintype "input"))
    )
    (net (code "50") (name "Net-(IC3A-A1)") (class "Default")
      (node (ref "IC3") (pin "7") (pinfunction "A1_7") (pintype "output"))
      (node (ref "IC6") (pin "9") (pinfunction "I0_9") (pintype "input"))
    )
    (net (code "51") (name "Net-(IC3A-A2)") (class "Default")
      (node (ref "IC3") (pin "6") (pinfunction "A2_6") (pintype "output"))
      (node (ref "IC6") (pin "4") (pinfunction "I0_4") (pintype "input"))
    )
    (net (code "52") (name "Net-(IC3A-EO)") (class "Default")
      (node (ref "IC3") (pin "15") (pinfunction "EO_15") (pintype "output"))
      (node (ref "IC4") (pin "5") (pinfunction "EI_5") (pintype "input"))
    )
    (net (code "53") (name "Net-(IC3A-GS)") (class "Default")
      (node (ref "IC3") (pin "14") (pinfunction "GS_14") (pintype "output"))
      (node (ref "IC6") (pin "1") (pinfunction "I0_1") (pintype "input"))
      (node (ref "IC7") (pin "1") (pinfunction "I0_1") (pintype "input"))
      (node (ref "IC7") (pin "2") (pinfunction "I1_2") (pintype "input"))
    )
    (net (code "54") (name "Net-(IC4A-0)") (class "Default")
      (node (ref "IC4") (pin "10") (pinfunction "0_10") (pintype "input"))
      (node (ref "S24") (pin "NO@1") (pinfunction "NO_NO@1") (pintype "passive"))
    )
    (net (code "55") (name "Net-(IC4A-1)") (class "Default")
      (node (ref "IC4") (pin "11") (pinfunction "1_11") (pintype "input"))
      (node (ref "S23") (pin "NO@1") (pinfunction "NO_NO@1") (pintype "passive"))
    )
    (net (code "56") (name "Net-(IC4A-2)") (class "Default")
      (node (ref "IC4") (pin "12") (pinfunction "2_12") (pintype "input"))
      (node (ref "S22") (pin "NO@1") (pinfunction "NO_NO@1") (pintype "passive"))
    )
    (net (code "57") (name "Net-(IC4A-3)") (class "Default")
      (node (ref "IC4") (pin "13") (pinfunction "3_13") (pintype "input"))
      (node (ref "S21") (pin "NO@1") (pinfunction "NO_NO@1") (pintype "passive"))
    )
    (net (code "58") (name "Net-(IC4A-4)") (class "Default")
      (node (ref "IC4") (pin "1") (pinfunction "4_1") (pintype "input"))
      (node (ref "S20") (pin "NO@1") (pinfunction "NO_NO@1") (pintype "passive"))
    )
    (net (code "59") (name "Net-(IC4A-5)") (class "Default")
      (node (ref "IC4") (pin "2") (pinfunction "5_2") (pintype "input"))
      (node (ref "S19") (pin "NO@1") (pinfunction "NO_NO@1") (pintype "passive"))
    )
    (net (code "60") (name "Net-(IC4A-6)") (class "Default")
      (node (ref "IC4") (pin "3") (pinfunction "6_3") (pintype "input"))
      (node (ref "S18") (pin "NO@1") (pinfunction "NO_NO@1") (pintype "passive"))
    )
    (net (code "61") (name "Net-(IC4A-7)") (class "Default")
      (node (ref "IC4") (pin "4") (pinfunction "7_4") (pintype "input"))
      (node (ref "S17") (pin "NO@1") (pinfunction "NO_NO@1") (pintype "passive"))
    )
    (net (code "62") (name "Net-(IC4A-A0)") (class "Default")
      (node (ref "IC4") (pin "9") (pinfunction "A0_9") (pintype "output"))
      (node (ref "IC6") (pin "13") (pinfunction "I1_13") (pintype "input"))
    )
    (net (code "63") (name "Net-(IC4A-A1)") (class "Default")
      (node (ref "IC4") (pin "7") (pinfunction "A1_7") (pintype "output"))
      (node (ref "IC6") (pin "10") (pinfunction "I1_10") (pintype "input"))
    )
    (net (code "64") (name "Net-(IC4A-A2)") (class "Default")
      (node (ref "IC4") (pin "6") (pinfunction "A2_6") (pintype "output"))
      (node (ref "IC6") (pin "5") (pinfunction "I1_5") (pintype "input"))
    )
    (net (code "65") (name "Net-(IC4A-GS)") (class "Default")
      (node (ref "IC4") (pin "14") (pinfunction "GS_14") (pintype "output"))
      (node (ref "IC6") (pin "2") (pinfunction "I1_2") (pintype "input"))
    )
    (net (code "66") (name "Net-(IC5A-I1)") (class "Default")
      (node (ref "IC5") (pin "2") (pinfunction "I1_2") (pintype "input"))
      (node (ref "IC6") (pin "3") (pinfunction "O_3") (pintype "output"))
    )
    (net (code "67") (name "Net-(IC6B-O)") (class "Default")
      (node (ref "IC6") (pin "6") (pinfunction "O_6") (pintype "output"))
      (node (ref "IC7") (pin "5") (pinfunction "I1_5") (pintype "input"))
    )
    (net (code "68") (name "Net-(IC6C-O)") (class "Default")
      (node (ref "IC6") (pin "8") (pinfunction "O_8") (pintype "output"))
      (node (ref "IC7") (pin "10") (pinfunction "I1_10") (pintype "input"))
    )
    (net (code "69") (name "Net-(IC6D-O)") (class "Default")
      (node (ref "IC6") (pin "11") (pinfunction "O_11") (pintype "output"))
      (node (ref "IC7") (pin "13") (pinfunction "I1_13") (pintype "input"))
    )
    (net (code "70") (name "Net-(IC8A-Y0)") (class "Default")
      (node (ref "IC8") (pin "15") (pinfunction "Y0_15") (pintype "output"))
      (node (ref "R33") (pin "2") (pinfunction "2_2") (pintype "passive"))
    )
    (net (code "71") (name "Net-(IC8A-Y1)") (class "Default")
      (node (ref "IC8") (pin "14") (pinfunction "Y1_14") (pintype "output"))
      (node (ref "R34") (pin "2") (pinfunction "2_2") (pintype "passive"))
    )
    (net (code "72") (name "Net-(IC8A-Y2)") (class "Default")
      (node (ref "IC8") (pin "13") (pinfunction "Y2_13") (pintype "output"))
      (node (ref "R35") (pin "2") (pinfunction "2_2") (pintype "passive"))
    )
    (net (code "73") (name "Net-(IC8A-Y3)") (class "Default")
      (node (ref "IC8") (pin "12") (pinfunction "Y3_12") (pintype "output"))
      (node (ref "R36") (pin "2") (pinfunction "2_2") (pintype "passive"))
    )
    (net (code "74") (name "Net-(IC8A-Y4)") (class "Default")
      (node (ref "IC8") (pin "11") (pinfunction "Y4_11") (pintype "output"))
      (node (ref "R37") (pin "2") (pinfunction "2_2") (pintype "passive"))
    )
    (net (code "75") (name "Net-(IC8A-Y5)") (class "Default")
      (node (ref "IC8") (pin "10") (pinfunction "Y5_10") (pintype "output"))
      (node (ref "R38") (pin "2") (pinfunction "2_2") (pintype "passive"))
    )
    (net (code "76") (name "Net-(IC8A-Y6)") (class "Default")
      (node (ref "IC8") (pin "9") (pinfunction "Y6_9") (pintype "output"))
      (node (ref "R39") (pin "2") (pinfunction "2_2") (pintype "passive"))
    )
    (net (code "77") (name "Net-(IC8A-Y7)") (class "Default")
      (node (ref "IC8") (pin "7") (pinfunction "Y7_7") (pintype "output"))
      (node (ref "R40") (pin "2") (pinfunction "2_2") (pintype "passive"))
    )
    (net (code "78") (name "Net-(IC9A-Y0)") (class "Default")
      (node (ref "IC9") (pin "15") (pinfunction "Y0_15") (pintype "output"))
      (node (ref "R25") (pin "2") (pinfunction "2_2") (pintype "passive"))
    )
    (net (code "79") (name "Net-(IC9A-Y1)") (class "Default")
      (node (ref "IC9") (pin "14") (pinfunction "Y1_14") (pintype "output"))
      (node (ref "R26") (pin "2") (pinfunction "2_2") (pintype "passive"))
    )
    (net (code "80") (name "Net-(IC9A-Y2)") (class "Default")
      (node (ref "IC9") (pin "13") (pinfunction "Y2_13") (pintype "output"))
      (node (ref "R27") (pin "2") (pinfunction "2_2") (pintype "passive"))
    )
    (net (code "81") (name "Net-(IC9A-Y3)") (class "Default")
      (node (ref "IC9") (pin "12") (pinfunction "Y3_12") (pintype "output"))
      (node (ref "R28") (pin "2") (pinfunction "2_2") (pintype "passive"))
    )
    (net (code "82") (name "Net-(IC9A-Y4)") (class "Default")
      (node (ref "IC9") (pin "11") (pinfunction "Y4_11") (pintype "output"))
      (node (ref "R29") (pin "2") (pinfunction "2_2") (pintype "passive"))
    )
    (net (code "83") (name "Net-(IC9A-Y5)") (class "Default")
      (node (ref "IC9") (pin "10") (pinfunction "Y5_10") (pintype "output"))
      (node (ref "R30") (pin "2") (pinfunction "2_2") (pintype "passive"))
    )
    (net (code "84") (name "Net-(IC9A-Y6)") (class "Default")
      (node (ref "IC9") (pin "9") (pinfunction "Y6_9") (pintype "output"))
      (node (ref "R31") (pin "2") (pinfunction "2_2") (pintype "passive"))
    )
    (net (code "85") (name "Net-(IC9A-Y7)") (class "Default")
      (node (ref "IC9") (pin "7") (pinfunction "Y7_7") (pintype "output"))
      (node (ref "R32") (pin "2") (pinfunction "2_2") (pintype "passive"))
    )
    (net (code "86") (name "Net-(IC15A-Y0)") (class "Default")
      (node (ref "IC15") (pin "15") (pinfunction "Y0_15") (pintype "output"))
      (node (ref "R41") (pin "2") (pinfunction "2_2") (pintype "passive"))
    )
    (net (code "87") (name "Net-(IC15A-Y1)") (class "Default")
      (node (ref "IC15") (pin "14") (pinfunction "Y1_14") (pintype "output"))
      (node (ref "R42") (pin "2") (pinfunction "2_2") (pintype "passive"))
    )
    (net (code "88") (name "Net-(IC15A-Y2)") (class "Default")
      (node (ref "IC15") (pin "13") (pinfunction "Y2_13") (pintype "output"))
      (node (ref "R43") (pin "2") (pinfunction "2_2") (pintype "passive"))
    )
    (net (code "89") (name "Net-(IC15A-Y3)") (class "Default")
      (node (ref "IC15") (pin "12") (pinfunction "Y3_12") (pintype "output"))
      (node (ref "R44") (pin "2") (pinfunction "2_2") (pintype "passive"))
    )
    (net (code "90") (name "Net-(IC15A-Y4)") (class "Default")
      (node (ref "IC15") (pin "11") (pinfunction "Y4_11") (pintype "output"))
      (node (ref "R45") (pin "2") (pinfunction "2_2") (pintype "passive"))
    )
    (net (code "91") (name "Net-(IC15A-Y5)") (class "Default")
      (node (ref "IC15") (pin "10") (pinfunction "Y5_10") (pintype "output"))
      (node (ref "R46") (pin "2") (pinfunction "2_2") (pintype "passive"))
    )
    (net (code "92") (name "Net-(IC15A-Y6)") (class "Default")
      (node (ref "IC15") (pin "9") (pinfunction "Y6_9") (pintype "output"))
      (node (ref "R47") (pin "2") (pinfunction "2_2") (pintype "passive"))
    )
    (net (code "93") (name "Net-(IC15A-Y7)") (class "Default")
      (node (ref "IC15") (pin "7") (pinfunction "Y7_7") (pintype "output"))
      (node (ref "R48") (pin "2") (pinfunction "2_2") (pintype "passive"))
    )
    (net (code "94") (name "Net-(LED1-C)") (class "Default")
      (node (ref "LED1") (pin "K") (pinfunction "C_K") (pintype "passive"))
      (node (ref "R25") (pin "1") (pinfunction "1_1") (pintype "passive"))
    )
    (net (code "95") (name "Net-(LED2-C)") (class "Default")
      (node (ref "LED2") (pin "K") (pinfunction "C_K") (pintype "passive"))
      (node (ref "R26") (pin "1") (pinfunction "1_1") (pintype "passive"))
    )
    (net (code "96") (name "Net-(LED3-C)") (class "Default")
      (node (ref "LED3") (pin "K") (pinfunction "C_K") (pintype "passive"))
      (node (ref "R27") (pin "1") (pinfunction "1_1") (pintype "passive"))
    )
    (net (code "97") (name "Net-(LED4-C)") (class "Default")
      (node (ref "LED4") (pin "K") (pinfunction "C_K") (pintype "passive"))
      (node (ref "R28") (pin "1") (pinfunction "1_1") (pintype "passive"))
    )
    (net (code "98") (name "Net-(LED5-C)") (class "Default")
      (node (ref "LED5") (pin "K") (pinfunction "C_K") (pintype "passive"))
      (node (ref "R29") (pin "1") (pinfunction "1_1") (pintype "passive"))
    )
    (net (code "99") (name "Net-(LED6-C)") (class "Default")
      (node (ref "LED6") (pin "K") (pinfunction "C_K") (pintype "passive"))
      (node (ref "R30") (pin "1") (pinfunction "1_1") (pintype "passive"))
    )
    (net (code "100") (name "Net-(LED7-C)") (class "Default")
      (node (ref "LED7") (pin "K") (pinfunction "C_K") (pintype "passive"))
      (node (ref "R31") (pin "1") (pinfunction "1_1") (pintype "passive"))
    )
    (net (code "101") (name "Net-(LED8-C)") (class "Default")
      (node (ref "LED8") (pin "K") (pinfunction "C_K") (pintype "passive"))
      (node (ref "R32") (pin "1") (pinfunction "1_1") (pintype "passive"))
    )
    (net (code "102") (name "Net-(LED9-C)") (class "Default")
      (node (ref "LED9") (pin "K") (pinfunction "C_K") (pintype "passive"))
      (node (ref "R33") (pin "1") (pinfunction "1_1") (pintype "passive"))
    )
    (net (code "103") (name "Net-(LED10-C)") (class "Default")
      (node (ref "LED10") (pin "K") (pinfunction "C_K") (pintype "passive"))
      (node (ref "R34") (pin "1") (pinfunction "1_1") (pintype "passive"))
    )
    (net (code "104") (name "Net-(LED11-C)") (class "Default")
      (node (ref "LED11") (pin "K") (pinfunction "C_K") (pintype "passive"))
      (node (ref "R35") (pin "1") (pinfunction "1_1") (pintype "passive"))
    )
    (net (code "105") (name "Net-(LED12-C)") (class "Default")
      (node (ref "LED12") (pin "K") (pinfunction "C_K") (pintype "passive"))
      (node (ref "R36") (pin "1") (pinfunction "1_1") (pintype "passive"))
    )
    (net (code "106") (name "Net-(LED13-C)") (class "Default")
      (node (ref "LED13") (pin "K") (pinfunction "C_K") (pintype "passive"))
      (node (ref "R37") (pin "1") (pinfunction "1_1") (pintype "passive"))
    )
    (net (code "107") (name "Net-(LED14-C)") (class "Default")
      (node (ref "LED14") (pin "K") (pinfunction "C_K") (pintype "passive"))
      (node (ref "R38") (pin "1") (pinfunction "1_1") (pintype "passive"))
    )
    (net (code "108") (name "Net-(LED15-C)") (class "Default")
      (node (ref "LED15") (pin "K") (pinfunction "C_K") (pintype "passive"))
      (node (ref "R39") (pin "1") (pinfunction "1_1") (pintype "passive"))
    )
    (net (code "109") (name "Net-(LED16-C)") (class "Default")
      (node (ref "LED16") (pin "K") (pinfunction "C_K") (pintype "passive"))
      (node (ref "R40") (pin "1") (pinfunction "1_1") (pintype "passive"))
    )
    (net (code "110") (name "Net-(LED17-C)") (class "Default")
      (node (ref "LED17") (pin "K") (pinfunction "C_K") (pintype "passive"))
      (node (ref "R41") (pin "1") (pinfunction "1_1") (pintype "passive"))
    )
    (net (code "111") (name "Net-(LED18-C)") (class "Default")
      (node (ref "LED18") (pin "K") (pinfunction "C_K") (pintype "passive"))
      (node (ref "R42") (pin "1") (pinfunction "1_1") (pintype "passive"))
    )
    (net (code "112") (name "Net-(LED19-C)") (class "Default")
      (node (ref "LED19") (pin "K") (pinfunction "C_K") (pintype "passive"))
      (node (ref "R43") (pin "1") (pinfunction "1_1") (pintype "passive"))
    )
    (net (code "113") (name "Net-(LED20-C)") (class "Default")
      (node (ref "LED20") (pin "K") (pinfunction "C_K") (pintype "passive"))
      (node (ref "R44") (pin "1") (pinfunction "1_1") (pintype "passive"))
    )
    (net (code "114") (name "Net-(LED21-C)") (class "Default")
      (node (ref "LED21") (pin "K") (pinfunction "C_K") (pintype "passive"))
      (node (ref "R45") (pin "1") (pinfunction "1_1") (pintype "passive"))
    )
    (net (code "115") (name "Net-(LED22-C)") (class "Default")
      (node (ref "LED22") (pin "K") (pinfunction "C_K") (pintype "passive"))
      (node (ref "R46") (pin "1") (pinfunction "1_1") (pintype "passive"))
    )
    (net (code "116") (name "Net-(LED23-C)") (class "Default")
      (node (ref "LED23") (pin "K") (pinfunction "C_K") (pintype "passive"))
      (node (ref "R47") (pin "1") (pinfunction "1_1") (pintype "passive"))
    )
    (net (code "117") (name "Net-(LED24-C)") (class "Default")
      (node (ref "LED24") (pin "K") (pinfunction "C_K") (pintype "passive"))
      (node (ref "R48") (pin "1") (pinfunction "1_1") (pintype "passive"))
    )
    (net (code "118") (name "Net-(R1-Pad1)") (class "Default")
      (node (ref "R1") (pin "1") (pinfunction "1_1") (pintype "passive"))
      (node (ref "S1") (pin "NO@2") (pinfunction "NO_NO@2") (pintype "passive"))
    )
    (net (code "119") (name "Net-(R2-Pad1)") (class "Default")
      (node (ref "R2") (pin "1") (pinfunction "1_1") (pintype "passive"))
      (node (ref "S2") (pin "NO@2") (pinfunction "NO_NO@2") (pintype "passive"))
    )
    (net (code "120") (name "Net-(R3-Pad1)") (class "Default")
      (node (ref "R3") (pin "1") (pinfunction "1_1") (pintype "passive"))
      (node (ref "S3") (pin "NO@2") (pinfunction "NO_NO@2") (pintype "passive"))
    )
    (net (code "121") (name "Net-(R4-Pad1)") (class "Default")
      (node (ref "R4") (pin "1") (pinfunction "1_1") (pintype "passive"))
      (node (ref "S4") (pin "NO@2") (pinfunction "NO_NO@2") (pintype "passive"))
    )
    (net (code "122") (name "Net-(R5-Pad1)") (class "Default")
      (node (ref "R5") (pin "1") (pinfunction "1_1") (pintype "passive"))
      (node (ref "S5") (pin "NO@2") (pinfunction "NO_NO@2") (pintype "passive"))
    )
    (net (code "123") (name "Net-(R6-Pad1)") (class "Default")
      (node (ref "R6") (pin "1") (pinfunction "1_1") (pintype "passive"))
      (node (ref "S6") (pin "NO@2") (pinfunction "NO_NO@2") (pintype "passive"))
    )
    (net (code "124") (name "Net-(R7-Pad1)") (class "Default")
      (node (ref "R7") (pin "1") (pinfunction "1_1") (pintype "passive"))
      (node (ref "S7") (pin "NO@2") (pinfunction "NO_NO@2") (pintype "passive"))
    )
    (net (code "125") (name "Net-(R8-Pad1)") (class "Default")
      (node (ref "R8") (pin "1") (pinfunction "1_1") (pintype "passive"))
      (node (ref "S8") (pin "NO@2") (pinfunction "NO_NO@2") (pintype "passive"))
    )
    (net (code "126") (name "Net-(R9-Pad1)") (class "Default")
      (node (ref "R9") (pin "1") (pinfunction "1_1") (pintype "passive"))
      (node (ref "S9") (pin "NO@2") (pinfunction "NO_NO@2") (pintype "passive"))
    )
    (net (code "127") (name "Net-(R10-Pad1)") (class "Default")
      (node (ref "R10") (pin "1") (pinfunction "1_1") (pintype "passive"))
      (node (ref "S10") (pin "NO@2") (pinfunction "NO_NO@2") (pintype "passive"))
    )
    (net (code "128") (name "Net-(R11-Pad1)") (class "Default")
      (node (ref "R11") (pin "1") (pinfunction "1_1") (pintype "passive"))
      (node (ref "S11") (pin "NO@2") (pinfunction "NO_NO@2") (pintype "passive"))
    )
    (net (code "129") (name "Net-(R12-Pad1)") (class "Default")
      (node (ref "R12") (pin "1") (pinfunction "1_1") (pintype "passive"))
      (node (ref "S12") (pin "NO@2") (pinfunction "NO_NO@2") (pintype "passive"))
    )
    (net (code "130") (name "Net-(R13-Pad1)") (class "Default")
      (node (ref "R13") (pin "1") (pinfunction "1_1") (pintype "passive"))
      (node (ref "S13") (pin "NO@2") (pinfunction "NO_NO@2") (pintype "passive"))
    )
    (net (code "131") (name "Net-(R14-Pad1)") (class "Default")
      (node (ref "R14") (pin "1") (pinfunction "1_1") (pintype "passive"))
      (node (ref "S14") (pin "NO@2") (pinfunction "NO_NO@2") (pintype "passive"))
    )
    (net (code "132") (name "Net-(R15-Pad1)") (class "Default")
      (node (ref "R15") (pin "1") (pinfunction "1_1") (pintype "passive"))
      (node (ref "S15") (pin "NO@2") (pinfunction "NO_NO@2") (pintype "passive"))
    )
    (net (code "133") (name "Net-(R16-Pad1)") (class "Default")
      (node (ref "R16") (pin "1") (pinfunction "1_1") (pintype "passive"))
      (node (ref "S16") (pin "NO@2") (pinfunction "NO_NO@2") (pintype "passive"))
    )
    (net (code "134") (name "Net-(R17-Pad1)") (class "Default")
      (node (ref "R17") (pin "1") (pinfunction "1_1") (pintype "passive"))
      (node (ref "S17") (pin "NO@2") (pinfunction "NO_NO@2") (pintype "passive"))
    )
    (net (code "135") (name "Net-(R18-Pad1)") (class "Default")
      (node (ref "R18") (pin "1") (pinfunction "1_1") (pintype "passive"))
      (node (ref "S18") (pin "NO@2") (pinfunction "NO_NO@2") (pintype "passive"))
    )
    (net (code "136") (name "Net-(R19-Pad1)") (class "Default")
      (node (ref "R19") (pin "1") (pinfunction "1_1") (pintype "passive"))
      (node (ref "S19") (pin "NO@2") (pinfunction "NO_NO@2") (pintype "passive"))
    )
    (net (code "137") (name "Net-(R20-Pad1)") (class "Default")
      (node (ref "R20") (pin "1") (pinfunction "1_1") (pintype "passive"))
      (node (ref "S20") (pin "NO@2") (pinfunction "NO_NO@2") (pintype "passive"))
    )
    (net (code "138") (name "Net-(R21-Pad1)") (class "Default")
      (node (ref "R21") (pin "1") (pinfunction "1_1") (pintype "passive"))
      (node (ref "S21") (pin "NO@2") (pinfunction "NO_NO@2") (pintype "passive"))
    )
    (net (code "139") (name "Net-(R22-Pad1)") (class "Default")
      (node (ref "R22") (pin "1") (pinfunction "1_1") (pintype "passive"))
      (node (ref "S22") (pin "NO@2") (pinfunction "NO_NO@2") (pintype "passive"))
    )
    (net (code "140") (name "Net-(R23-Pad1)") (class "Default")
      (node (ref "R23") (pin "1") (pinfunction "1_1") (pintype "passive"))
      (node (ref "S23") (pin "NO@2") (pinfunction "NO_NO@2") (pintype "passive"))
    )
    (net (code "141") (name "Net-(R24-Pad1)") (class "Default")
      (node (ref "R24") (pin "1") (pinfunction "1_1") (pintype "passive"))
      (node (ref "S24") (pin "NO@2") (pinfunction "NO_NO@2") (pintype "passive"))
    )
    (net (code "142") (name "VCC") (class "Default")
      (node (ref "C1") (pin "1") (pinfunction "1_1") (pintype "passive"))
      (node (ref "C10") (pin "1") (pinfunction "1_1") (pintype "passive"))
      (node (ref "C11") (pin "1") (pinfunction "1_1") (pintype "passive"))
      (node (ref "C12") (pin "1") (pinfunction "1_1") (pintype "passive"))
      (node (ref "C2") (pin "1") (pinfunction "1_1") (pintype "passive"))
      (node (ref "C3") (pin "1") (pinfunction "1_1") (pintype "passive"))
      (node (ref "C4") (pin "1") (pinfunction "1_1") (pintype "passive"))
      (node (ref "C6") (pin "1") (pinfunction "1_1") (pintype "passive"))
      (node (ref "C7") (pin "1") (pinfunction "1_1") (pintype "passive"))
      (node (ref "C8") (pin "1") (pinfunction "1_1") (pintype "passive"))
      (node (ref "C9") (pin "1") (pinfunction "1_1") (pintype "passive"))
      (node (ref "IC1") (pin "20") (pinfunction "VCC_20") (pintype "power_in"))
      (node (ref "IC15") (pin "16") (pinfunction "VCC_16") (pintype "power_in"))
      (node (ref "IC2") (pin "16") (pinfunction "VCC_16") (pintype "power_in"))
      (node (ref "IC3") (pin "16") (pinfunction "VCC_16") (pintype "power_in"))
      (node (ref "IC4") (pin "16") (pinfunction "VCC_16") (pintype "power_in"))
      (node (ref "IC5") (pin "14") (pinfunction "VCC_14") (pintype "power_in"))
      (node (ref "IC6") (pin "14") (pinfunction "VCC_14") (pintype "power_in"))
      (node (ref "IC7") (pin "14") (pinfunction "VCC_14") (pintype "power_in"))
      (node (ref "IC8") (pin "16") (pinfunction "VCC_16") (pintype "power_in"))
      (node (ref "IC9") (pin "16") (pinfunction "VCC_16") (pintype "power_in"))
      (node (ref "IC9") (pin "6") (pinfunction "G1_6") (pintype "input"))
      (node (ref "JP1") (pin "2") (pinfunction "2_2") (pintype "passive"))
      (node (ref "JP2") (pin "10") (pinfunction "10_10") (pintype "passive"))
      (node (ref "JP5") (pin "2") (pinfunction "2_2") (pintype "passive"))
      (node (ref "LED1") (pin "A") (pinfunction "A_A") (pintype "passive"))
      (node (ref "LED10") (pin "A") (pinfunction "A_A") (pintype "passive"))
      (node (ref "LED11") (pin "A") (pinfunction "A_A") (pintype "passive"))
      (node (ref "LED12") (pin "A") (pinfunction "A_A") (pintype "passive"))
      (node (ref "LED13") (pin "A") (pinfunction "A_A") (pintype "passive"))
      (node (ref "LED14") (pin "A") (pinfunction "A_A") (pintype "passive"))
      (node (ref "LED15") (pin "A") (pinfunction "A_A") (pintype "passive"))
      (node (ref "LED16") (pin "A") (pinfunction "A_A") (pintype "passive"))
      (node (ref "LED17") (pin "A") (pinfunction "A_A") (pintype "passive"))
      (node (ref "LED18") (pin "A") (pinfunction "A_A") (pintype "passive"))
      (node (ref "LED19") (pin "A") (pinfunction "A_A") (pintype "passive"))
      (node (ref "LED2") (pin "A") (pinfunction "A_A") (pintype "passive"))
      (node (ref "LED20") (pin "A") (pinfunction "A_A") (pintype "passive"))
      (node (ref "LED21") (pin "A") (pinfunction "A_A") (pintype "passive"))
      (node (ref "LED22") (pin "A") (pinfunction "A_A") (pintype "passive"))
      (node (ref "LED23") (pin "A") (pinfunction "A_A") (pintype "passive"))
      (node (ref "LED24") (pin "A") (pinfunction "A_A") (pintype "passive"))
      (node (ref "LED3") (pin "A") (pinfunction "A_A") (pintype "passive"))
      (node (ref "LED4") (pin "A") (pinfunction "A_A") (pintype "passive"))
      (node (ref "LED5") (pin "A") (pinfunction "A_A") (pintype "passive"))
      (node (ref "LED6") (pin "A") (pinfunction "A_A") (pintype "passive"))
      (node (ref "LED7") (pin "A") (pinfunction "A_A") (pintype "passive"))
      (node (ref "LED8") (pin "A") (pinfunction "A_A") (pintype "passive"))
      (node (ref "LED9") (pin "A") (pinfunction "A_A") (pintype "passive"))
      (node (ref "R1") (pin "2") (pinfunction "2_2") (pintype "passive"))
      (node (ref "R10") (pin "2") (pinfunction "2_2") (pintype "passive"))
      (node (ref "R11") (pin "2") (pinfunction "2_2") (pintype "passive"))
      (node (ref "R12") (pin "2") (pinfunction "2_2") (pintype "passive"))
      (node (ref "R13") (pin "2") (pinfunction "2_2") (pintype "passive"))
      (node (ref "R14") (pin "2") (pinfunction "2_2") (pintype "passive"))
      (node (ref "R15") (pin "2") (pinfunction "2_2") (pintype "passive"))
      (node (ref "R16") (pin "2") (pinfunction "2_2") (pintype "passive"))
      (node (ref "R17") (pin "2") (pinfunction "2_2") (pintype "passive"))
      (node (ref "R18") (pin "2") (pinfunction "2_2") (pintype "passive"))
      (node (ref "R19") (pin "2") (pinfunction "2_2") (pintype "passive"))
      (node (ref "R2") (pin "2") (pinfunction "2_2") (pintype "passive"))
      (node (ref "R20") (pin "2") (pinfunction "2_2") (pintype "passive"))
      (node (ref "R21") (pin "2") (pinfunction "2_2") (pintype "passive"))
      (node (ref "R22") (pin "2") (pinfunction "2_2") (pintype "passive"))
      (node (ref "R23") (pin "2") (pinfunction "2_2") (pintype "passive"))
      (node (ref "R24") (pin "2") (pinfunction "2_2") (pintype "passive"))
      (node (ref "R3") (pin "2") (pinfunction "2_2") (pintype "passive"))
      (node (ref "R4") (pin "2") (pinfunction "2_2") (pintype "passive"))
      (node (ref "R5") (pin "2") (pinfunction "2_2") (pintype "passive"))
      (node (ref "R6") (pin "2") (pinfunction "2_2") (pintype "passive"))
      (node (ref "R7") (pin "2") (pinfunction "2_2") (pintype "passive"))
      (node (ref "R8") (pin "2") (pinfunction "2_2") (pintype "passive"))
      (node (ref "R9") (pin "2") (pinfunction "2_2") (pintype "passive"))
    )
    (net (code "143") (name "unconnected-(IC4A-EO-Pad15)") (class "Default")
      (node (ref "IC4") (pin "15") (pinfunction "EO_15") (pintype "output"))
    )
  )
)
